# 1-Schematic_ReflowPlate.net
KiCad netlist of a schematic drawn in EasyEDA
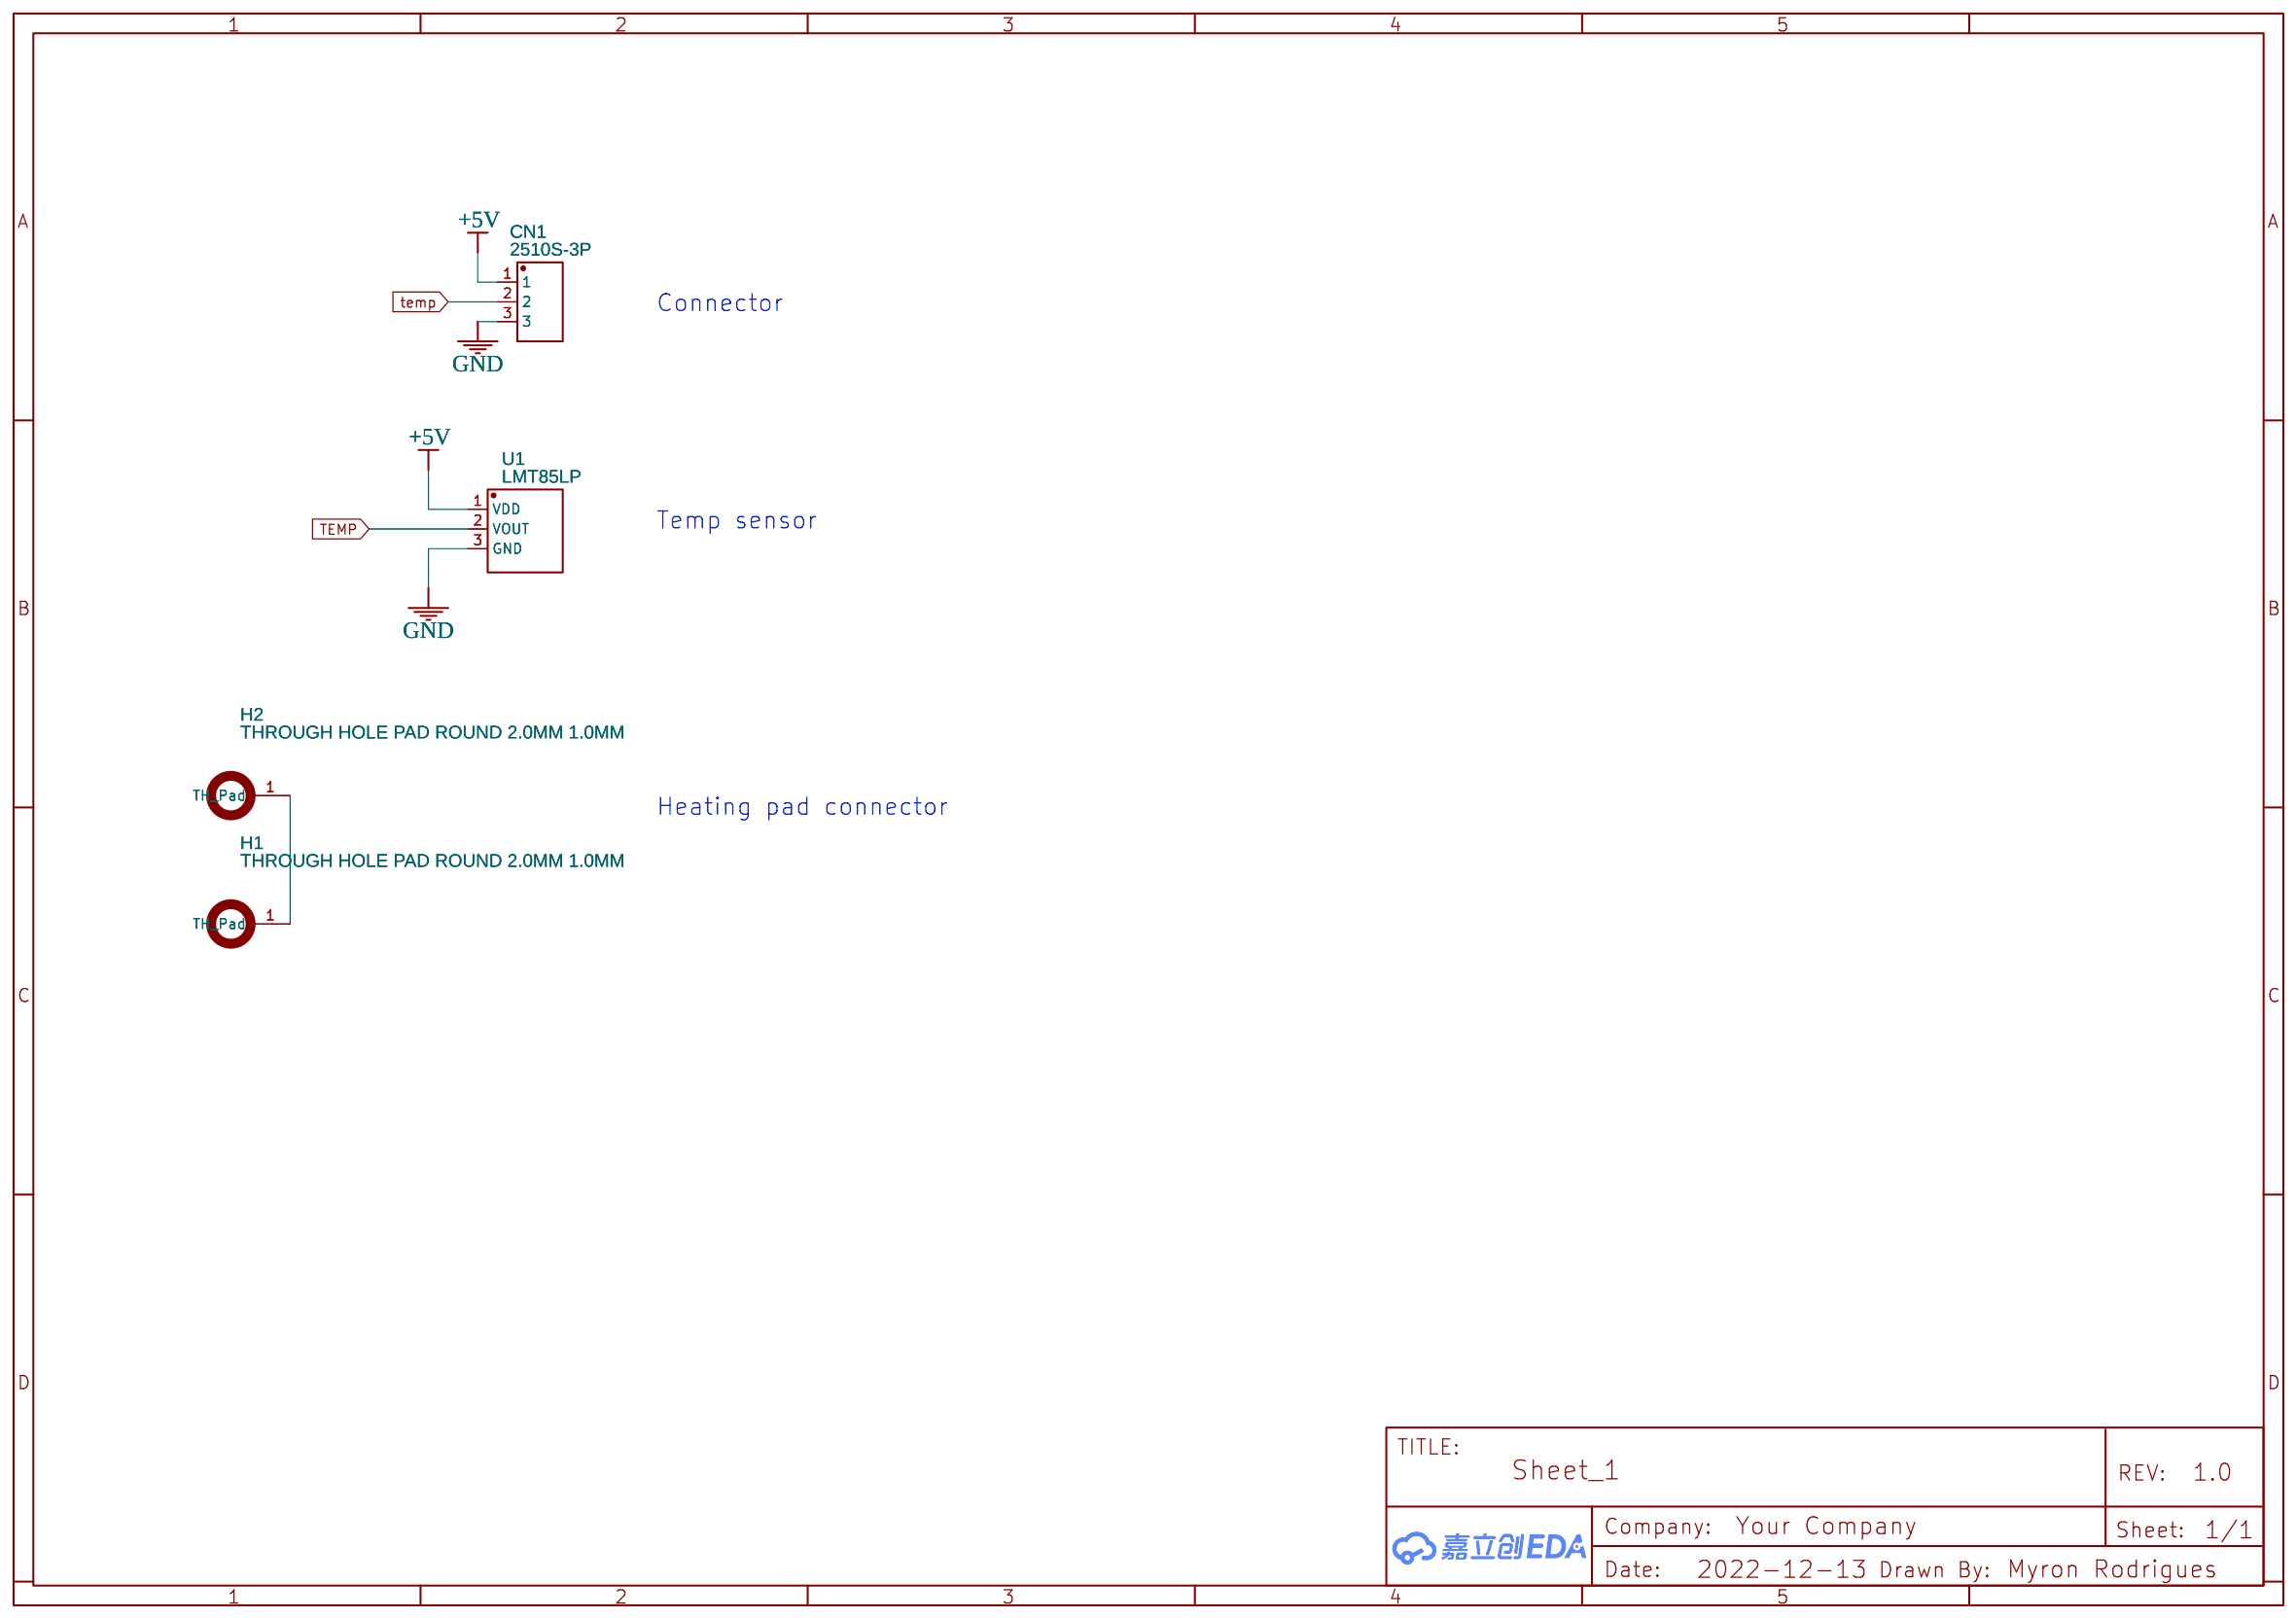
[diagram p0: schematic sheet]

(export (version "E")
  (design (tool "Eeschema 10.0.6"))
  (components
    (comp (ref "CN1")
      (value "2510S-3P")
      (fields
        (field (name "BOM_Manufacturer Part") "W-2510S03P-0000")
        (field (name "BOM_Supplier Part") "C132505")
      )
      (libsource (lib "") (part "2510S-3P"))
    )
    (comp (ref "H1")
      (value "THROUGH HOLE PAD ROUND 2.0MM 1.0MM")
      (libsource (lib "") (part "THROUGH HOLE PAD ROUND 2.0MM 1.0MM"))
    )
    (comp (ref "H2")
      (value "THROUGH HOLE PAD ROUND 2.0MM 1.0MM")
      (libsource (lib "") (part "THROUGH HOLE PAD ROUND 2.0MM 1.0MM"))
    )
    (comp (ref "U1")
      (value "LMT85LP")
      (fields (field (name "BOM_Supplier Part") "C75856"))
      (libsource (lib "") (part "LMT85LP"))
    )
  )
  (nets
    (net (code "1") (name "+5V") (class "Default")
      (node (ref "CN1") (pin "1") (pinfunction "1_1") (pintype "unspecified"))
      (node (ref "U1") (pin "1") (pinfunction "VDD_1") (pintype "unspecified"))
    )
    (net (code "2") (name "GND") (class "Default")
      (node (ref "CN1") (pin "3") (pinfunction "3_3") (pintype "unspecified"))
      (node (ref "U1") (pin "3") (pinfunction "GND_3") (pintype "unspecified"))
    )
    (net (code "3") (name "Net-(H1-TH_Pad)") (class "Default")
      (node (ref "H1") (pin "1") (pinfunction "TH_Pad_1") (pintype "unspecified"))
      (node (ref "H2") (pin "1") (pinfunction "TH_Pad_1") (pintype "unspecified"))
    )
    (net (code "4") (name "TEMP") (class "Default")
      (node (ref "U1") (pin "2") (pinfunction "VOUT_2") (pintype "unspecified"))
    )
    (net (code "5") (name "temp") (class "Default")
      (node (ref "CN1") (pin "2") (pinfunction "2_2") (pintype "unspecified"))
    )
  )
)
